# RFBoardLayoutGen0_v03_3JK2.net
KiCad netlist of a schematic drawn in EAGLE
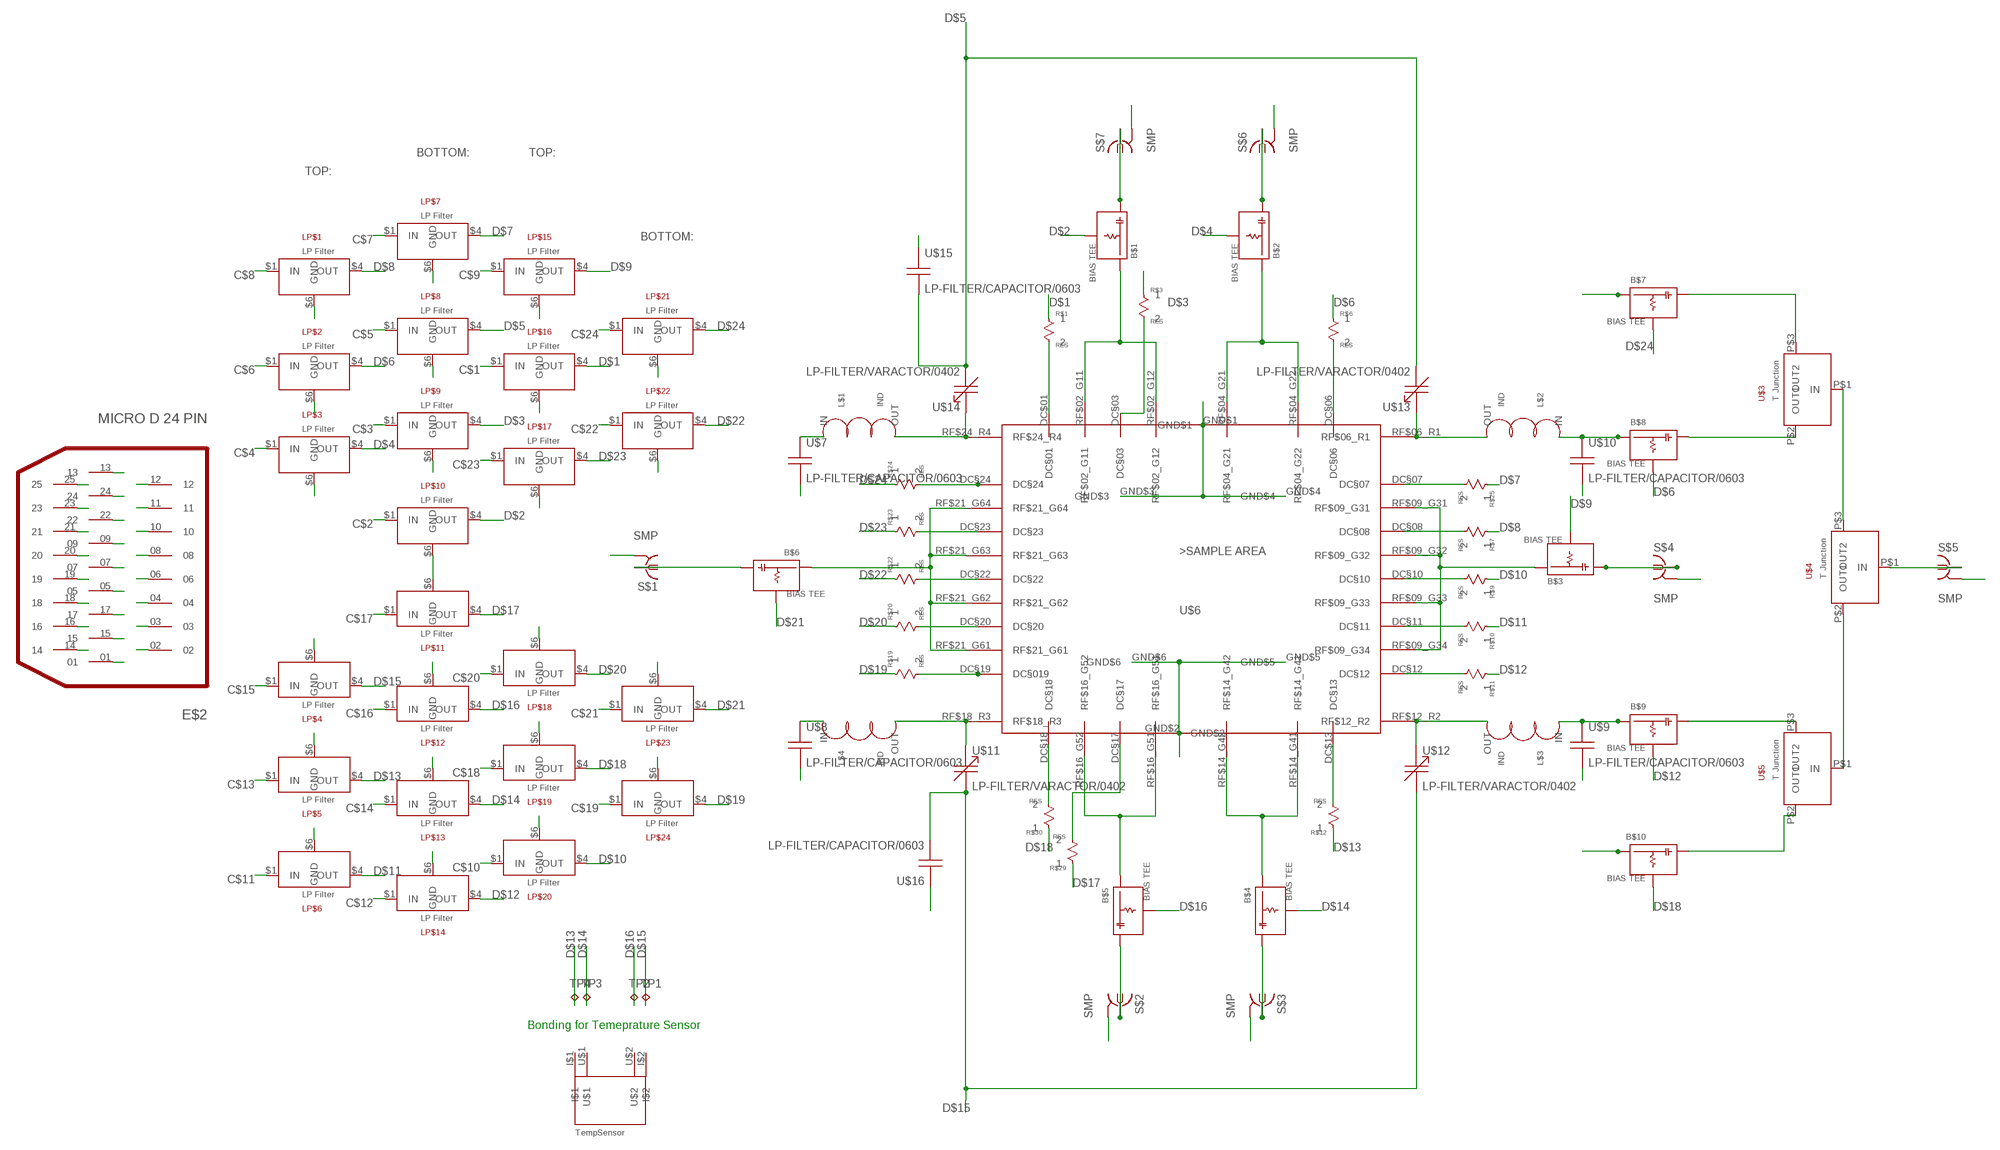
[diagram p0: schematic, sheet 1, part 1 of 2]
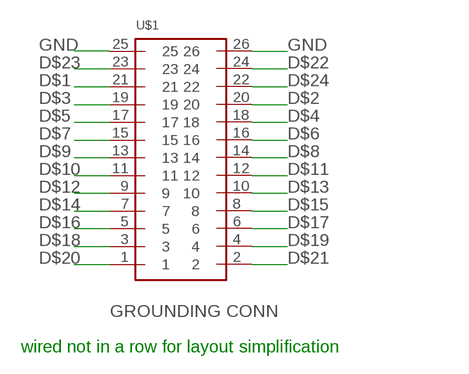
[diagram p1: schematic, sheet 1, part 2 of 2]

(export (version "E")
  (design (tool "Eeschema 10.0.6"))
  (components
    (comp (ref "B$1")
      (value "BIASTEEDOWN")
      (footprint "eagle-import:BIAS_TEE_DOWN_0603")
      (libsource (lib "eagle-import") (part "BIASTEEDOWN"))
    )
    (comp (ref "B$2")
      (value "BIASTEEUP")
      (footprint "eagle-import:BIAS_TEE_UP_0603")
      (libsource (lib "eagle-import") (part "BIASTEEUP"))
    )
    (comp (ref "B$3")
      (value "BIASTEEDOWN")
      (footprint "eagle-import:BIAS_TEE_DOWN_0603")
      (libsource (lib "eagle-import") (part "BIASTEEDOWN"))
    )
    (comp (ref "B$4")
      (value "BIASTEEDOWN")
      (footprint "eagle-import:BIAS_TEE_DOWN_0603")
      (libsource (lib "eagle-import") (part "BIASTEEDOWN"))
    )
    (comp (ref "B$5")
      (value "BIASTEEUP")
      (footprint "eagle-import:BIAS_TEE_UP_0603")
      (libsource (lib "eagle-import") (part "BIASTEEUP"))
    )
    (comp (ref "B$6")
      (value "BIASTEEDOWN")
      (footprint "eagle-import:BIAS_TEE_DOWN_0603")
      (libsource (lib "eagle-import") (part "BIASTEEDOWN"))
    )
    (comp (ref "B$7")
      (value "BIASTEEUP")
      (footprint "eagle-import:BIAS_TEE_UP_0603")
      (libsource (lib "eagle-import") (part "BIASTEEUP"))
    )
    (comp (ref "B$8")
      (value "BIASTEEDOWN")
      (footprint "eagle-import:BIAS_TEE_DOWN_0603")
      (libsource (lib "eagle-import") (part "BIASTEEDOWN"))
    )
    (comp (ref "B$9")
      (value "BIASTEEUP")
      (footprint "eagle-import:BIAS_TEE_UP_0603")
      (libsource (lib "eagle-import") (part "BIASTEEUP"))
    )
    (comp (ref "B$10")
      (value "BIASTEEDOWN")
      (footprint "eagle-import:BIAS_TEE_DOWN_0603")
      (libsource (lib "eagle-import") (part "BIASTEEDOWN"))
    )
    (comp (ref "E$2")
      (value "25_SOCKET_M83513(13-DPINOUT2")
      (footprint "eagle-import:25_SOCKET_M83513_13-D_V2")
      (libsource (lib "eagle-import") (part "25_SOCKET_M83513(13-DPINOUT2"))
    )
    (comp (ref "L$1")
      (value "L_MATCH")
      (footprint "eagle-import:L_MATCH")
      (libsource (lib "eagle-import") (part "L_MATCH"))
    )
    (comp (ref "L$2")
      (value "L_MATCH")
      (footprint "eagle-import:L_MATCH")
      (libsource (lib "eagle-import") (part "L_MATCH"))
    )
    (comp (ref "L$3")
      (value "L_MATCH")
      (footprint "eagle-import:L_MATCH")
      (libsource (lib "eagle-import") (part "L_MATCH"))
    )
    (comp (ref "L$4")
      (value "L_MATCH")
      (footprint "eagle-import:L_MATCH")
      (libsource (lib "eagle-import") (part "L_MATCH"))
    )
    (comp (ref "LP$1")
      (value "LP-FILTER/1-STAGETOP")
      (footprint "eagle-import:LP-FILTER_1_STAGE_OS_0603_TOP")
      (libsource (lib "eagle-import") (part "LP-FILTER/1-STAGETOP"))
    )
    (comp (ref "LP$2")
      (value "LP-FILTER/1-STAGETOP")
      (footprint "eagle-import:LP-FILTER_1_STAGE_OS_0603_TOP")
      (libsource (lib "eagle-import") (part "LP-FILTER/1-STAGETOP"))
    )
    (comp (ref "LP$3")
      (value "LP-FILTER/1-STAGETOP")
      (footprint "eagle-import:LP-FILTER_1_STAGE_OS_0603_TOP")
      (libsource (lib "eagle-import") (part "LP-FILTER/1-STAGETOP"))
    )
    (comp (ref "LP$4")
      (value "LP-FILTER/1-STAGETOP")
      (footprint "eagle-import:LP-FILTER_1_STAGE_OS_0603_TOP")
      (libsource (lib "eagle-import") (part "LP-FILTER/1-STAGETOP"))
    )
    (comp (ref "LP$5")
      (value "LP-FILTER/1-STAGETOP")
      (footprint "eagle-import:LP-FILTER_1_STAGE_OS_0603_TOP")
      (libsource (lib "eagle-import") (part "LP-FILTER/1-STAGETOP"))
    )
    (comp (ref "LP$6")
      (value "LP-FILTER/1-STAGETOP")
      (footprint "eagle-import:LP-FILTER_1_STAGE_OS_0603_TOP")
      (libsource (lib "eagle-import") (part "LP-FILTER/1-STAGETOP"))
    )
    (comp (ref "LP$7")
      (value "LP-FILTER/1-STAGEBOT")
      (footprint "eagle-import:LP-FILTER_1_STAGE_OS_0603_BOTTOM")
      (libsource (lib "eagle-import") (part "LP-FILTER/1-STAGEBOT"))
    )
    (comp (ref "LP$8")
      (value "LP-FILTER/1-STAGEBOT")
      (footprint "eagle-import:LP-FILTER_1_STAGE_OS_0603_BOTTOM")
      (libsource (lib "eagle-import") (part "LP-FILTER/1-STAGEBOT"))
    )
    (comp (ref "LP$9")
      (value "LP-FILTER/1-STAGEBOT")
      (footprint "eagle-import:LP-FILTER_1_STAGE_OS_0603_BOTTOM")
      (libsource (lib "eagle-import") (part "LP-FILTER/1-STAGEBOT"))
    )
    (comp (ref "LP$10")
      (value "LP-FILTER/1-STAGEBOT")
      (footprint "eagle-import:LP-FILTER_1_STAGE_OS_0603_BOTTOM")
      (libsource (lib "eagle-import") (part "LP-FILTER/1-STAGEBOT"))
    )
    (comp (ref "LP$11")
      (value "LP-FILTER/1-STAGEBOT")
      (footprint "eagle-import:LP-FILTER_1_STAGE_OS_0603_BOTTOM")
      (libsource (lib "eagle-import") (part "LP-FILTER/1-STAGEBOT"))
    )
    (comp (ref "LP$12")
      (value "LP-FILTER/1-STAGEBOT")
      (footprint "eagle-import:LP-FILTER_1_STAGE_OS_0603_BOTTOM")
      (libsource (lib "eagle-import") (part "LP-FILTER/1-STAGEBOT"))
    )
    (comp (ref "LP$13")
      (value "LP-FILTER/1-STAGEBOT")
      (footprint "eagle-import:LP-FILTER_1_STAGE_OS_0603_BOTTOM")
      (libsource (lib "eagle-import") (part "LP-FILTER/1-STAGEBOT"))
    )
    (comp (ref "LP$14")
      (value "LP-FILTER/1-STAGEBOT")
      (footprint "eagle-import:LP-FILTER_1_STAGE_OS_0603_BOTTOM")
      (libsource (lib "eagle-import") (part "LP-FILTER/1-STAGEBOT"))
    )
    (comp (ref "LP$15")
      (value "LP-FILTER/1-STAGETOP")
      (footprint "eagle-import:LP-FILTER_1_STAGE_OS_0603_TOP")
      (libsource (lib "eagle-import") (part "LP-FILTER/1-STAGETOP"))
    )
    (comp (ref "LP$16")
      (value "LP-FILTER/1-STAGETOP")
      (footprint "eagle-import:LP-FILTER_1_STAGE_OS_0603_TOP")
      (libsource (lib "eagle-import") (part "LP-FILTER/1-STAGETOP"))
    )
    (comp (ref "LP$17")
      (value "LP-FILTER/1-STAGETOP")
      (footprint "eagle-import:LP-FILTER_1_STAGE_OS_0603_TOP")
      (libsource (lib "eagle-import") (part "LP-FILTER/1-STAGETOP"))
    )
    (comp (ref "LP$18")
      (value "LP-FILTER/1-STAGETOP")
      (footprint "eagle-import:LP-FILTER_1_STAGE_OS_0603_TOP")
      (libsource (lib "eagle-import") (part "LP-FILTER/1-STAGETOP"))
    )
    (comp (ref "LP$19")
      (value "LP-FILTER/1-STAGETOP")
      (footprint "eagle-import:LP-FILTER_1_STAGE_OS_0603_TOP")
      (libsource (lib "eagle-import") (part "LP-FILTER/1-STAGETOP"))
    )
    (comp (ref "LP$20")
      (value "LP-FILTER/1-STAGETOP")
      (footprint "eagle-import:LP-FILTER_1_STAGE_OS_0603_TOP")
      (libsource (lib "eagle-import") (part "LP-FILTER/1-STAGETOP"))
    )
    (comp (ref "LP$21")
      (value "LP-FILTER/1-STAGEBOT")
      (footprint "eagle-import:LP-FILTER_1_STAGE_OS_0603_BOTTOM")
      (libsource (lib "eagle-import") (part "LP-FILTER/1-STAGEBOT"))
    )
    (comp (ref "LP$22")
      (value "LP-FILTER/1-STAGEBOT")
      (footprint "eagle-import:LP-FILTER_1_STAGE_OS_0603_BOTTOM")
      (libsource (lib "eagle-import") (part "LP-FILTER/1-STAGEBOT"))
    )
    (comp (ref "LP$23")
      (value "LP-FILTER/1-STAGEBOT")
      (footprint "eagle-import:LP-FILTER_1_STAGE_OS_0603_BOTTOM")
      (libsource (lib "eagle-import") (part "LP-FILTER/1-STAGEBOT"))
    )
    (comp (ref "LP$24")
      (value "LP-FILTER/1-STAGEBOT")
      (footprint "eagle-import:LP-FILTER_1_STAGE_OS_0603_BOTTOM")
      (libsource (lib "eagle-import") (part "LP-FILTER/1-STAGEBOT"))
    )
    (comp (ref "R$1")
      (value "10K")
      (footprint "eagle-import:LP-FILTER_RESISTOR_0603_BOTTOM")
      (libsource (lib "eagle-import") (part "LP-FILTER/RESISTOR/0603"))
    )
    (comp (ref "R$3")
      (value "10K")
      (footprint "eagle-import:LP-FILTER_RESISTOR_0603_BOTTOM")
      (libsource (lib "eagle-import") (part "LP-FILTER/RESISTOR/0603"))
    )
    (comp (ref "R$6")
      (value "10K")
      (footprint "eagle-import:LP-FILTER_RESISTOR_0603_BOTTOM")
      (libsource (lib "eagle-import") (part "LP-FILTER/RESISTOR/0603"))
    )
    (comp (ref "R$7")
      (value "10K")
      (footprint "eagle-import:LP-FILTER_RESISTOR_0603_BOTTOM")
      (libsource (lib "eagle-import") (part "LP-FILTER/RESISTOR/0603"))
    )
    (comp (ref "R$9")
      (value "10K")
      (footprint "eagle-import:LP-FILTER_RESISTOR_0603_BOTTOM")
      (libsource (lib "eagle-import") (part "LP-FILTER/RESISTOR/0603"))
    )
    (comp (ref "R$10")
      (value "10K")
      (footprint "eagle-import:LP-FILTER_RESISTOR_0603_BOTTOM")
      (libsource (lib "eagle-import") (part "LP-FILTER/RESISTOR/0603"))
    )
    (comp (ref "R$11")
      (value "10K")
      (footprint "eagle-import:LP-FILTER_RESISTOR_0603_BOTTOM")
      (libsource (lib "eagle-import") (part "LP-FILTER/RESISTOR/0603"))
    )
    (comp (ref "R$12")
      (value "10K")
      (footprint "eagle-import:LP-FILTER_RESISTOR_0603_BOTTOM")
      (libsource (lib "eagle-import") (part "LP-FILTER/RESISTOR/0603"))
    )
    (comp (ref "R$19")
      (value "10K")
      (footprint "eagle-import:LP-FILTER_RESISTOR_0603_BOTTOM")
      (libsource (lib "eagle-import") (part "LP-FILTER/RESISTOR/0603"))
    )
    (comp (ref "R$20")
      (value "10K")
      (footprint "eagle-import:LP-FILTER_RESISTOR_0603_BOTTOM")
      (libsource (lib "eagle-import") (part "LP-FILTER/RESISTOR/0603"))
    )
    (comp (ref "R$22")
      (value "10K")
      (footprint "eagle-import:LP-FILTER_RESISTOR_0603_BOTTOM")
      (libsource (lib "eagle-import") (part "LP-FILTER/RESISTOR/0603"))
    )
    (comp (ref "R$23")
      (value "10K")
      (footprint "eagle-import:LP-FILTER_RESISTOR_0603_BOTTOM")
      (libsource (lib "eagle-import") (part "LP-FILTER/RESISTOR/0603"))
    )
    (comp (ref "R$24")
      (value "10K")
      (footprint "eagle-import:LP-FILTER_RESISTOR_0603_BOTTOM")
      (libsource (lib "eagle-import") (part "LP-FILTER/RESISTOR/0603"))
    )
    (comp (ref "R$25")
      (value "10K")
      (footprint "eagle-import:LP-FILTER_RESISTOR_0603_BOTTOM")
      (libsource (lib "eagle-import") (part "LP-FILTER/RESISTOR/0603"))
    )
    (comp (ref "R$29")
      (value "10K")
      (footprint "eagle-import:LP-FILTER_RESISTOR_0603_BOTTOM")
      (libsource (lib "eagle-import") (part "LP-FILTER/RESISTOR/0603"))
    )
    (comp (ref "R$30")
      (value "10K")
      (footprint "eagle-import:LP-FILTER_RESISTOR_0603_BOTTOM")
      (libsource (lib "eagle-import") (part "LP-FILTER/RESISTOR/0603"))
    )
    (comp (ref "S$1")
      (value "MC-921WIDE")
      (footprint "eagle-import:SMP_STRAIGHT_MINI_WIDE")
      (libsource (lib "eagle-import") (part "MC-921WIDE"))
    )
    (comp (ref "S$2")
      (value "MC-921WIDE")
      (footprint "eagle-import:SMP_STRAIGHT_MINI_WIDE")
      (libsource (lib "eagle-import") (part "MC-921WIDE"))
    )
    (comp (ref "S$3")
      (value "MC-921WIDE")
      (footprint "eagle-import:SMP_STRAIGHT_MINI_WIDE")
      (libsource (lib "eagle-import") (part "MC-921WIDE"))
    )
    (comp (ref "S$4")
      (value "MC-921WIDE")
      (footprint "eagle-import:SMP_STRAIGHT_MINI_WIDE")
      (libsource (lib "eagle-import") (part "MC-921WIDE"))
    )
    (comp (ref "S$5")
      (value "MC-921WIDE")
      (footprint "eagle-import:SMP_STRAIGHT_MINI_WIDE")
      (libsource (lib "eagle-import") (part "MC-921WIDE"))
    )
    (comp (ref "S$6")
      (value "MC-921WIDE")
      (footprint "eagle-import:SMP_STRAIGHT_MINI_WIDE")
      (libsource (lib "eagle-import") (part "MC-921WIDE"))
    )
    (comp (ref "S$7")
      (value "MC-921WIDE")
      (footprint "eagle-import:SMP_STRAIGHT_MINI_WIDE")
      (libsource (lib "eagle-import") (part "MC-921WIDE"))
    )
    (comp (ref "TP1")
      (value "TPTP07SQ")
      (footprint "eagle-import:TP07SQ")
      (libsource (lib "eagle-import") (part "TPTP07SQ"))
    )
    (comp (ref "TP2")
      (value "TPTP07SQ")
      (footprint "eagle-import:TP07SQ")
      (libsource (lib "eagle-import") (part "TPTP07SQ"))
    )
    (comp (ref "TP3")
      (value "TPTP07SQ")
      (footprint "eagle-import:TP07SQ")
      (libsource (lib "eagle-import") (part "TPTP07SQ"))
    )
    (comp (ref "TP4")
      (value "TPTP07SQ")
      (footprint "eagle-import:TP07SQ")
      (libsource (lib "eagle-import") (part "TPTP07SQ"))
    )
    (comp (ref "U$1")
      (value "MEC8-113-02-L-D-RA1MBRD")
      (footprint "eagle-import:MEC8-113-02-L-D-RA1")
      (libsource (lib "eagle-import") (part "MEC8-113-02-L-D-RA1MBRD"))
    )
    (comp (ref "U$2")
      (value "TEMPSENS")
      (footprint "eagle-import:RX-BR_V1")
      (libsource (lib "eagle-import") (part "TEMPSENS"))
    )
    (comp (ref "U$3")
      (value "TJUNCTION")
      (footprint "eagle-import:T_JUNCTION_0.3MM")
      (libsource (lib "eagle-import") (part "TJUNCTION"))
    )
    (comp (ref "U$4")
      (value "TJUNCTION")
      (footprint "eagle-import:T_JUNCTION_0.3MM")
      (libsource (lib "eagle-import") (part "TJUNCTION"))
    )
    (comp (ref "U$5")
      (value "TJUNCTION")
      (footprint "eagle-import:T_JUNCTION_0.3MM")
      (libsource (lib "eagle-import") (part "TJUNCTION"))
    )
    (comp (ref "U$6")
      (value "24DC+10RF_V2.0")
      (footprint "eagle-import:24DC+10RF_400MU-PADS_0.7X0.7_V2.0")
      (libsource (lib "eagle-import") (part "24DC+10RF_V2.0"))
    )
    (comp (ref "U$7")
      (value "LP-FILTER/CAPACITOR/0603")
      (footprint "eagle-import:LP-FILTER_CAPACITOR_0603_BOTTOM")
      (libsource (lib "eagle-import") (part "LP-FILTER/CAPACITOR/0603"))
    )
    (comp (ref "U$8")
      (value "LP-FILTER/CAPACITOR/0603")
      (footprint "eagle-import:LP-FILTER_CAPACITOR_0603_BOTTOM")
      (libsource (lib "eagle-import") (part "LP-FILTER/CAPACITOR/0603"))
    )
    (comp (ref "U$9")
      (value "LP-FILTER/CAPACITOR/0603")
      (footprint "eagle-import:LP-FILTER_CAPACITOR_0603_BOTTOM")
      (libsource (lib "eagle-import") (part "LP-FILTER/CAPACITOR/0603"))
    )
    (comp (ref "U$10")
      (value "LP-FILTER/CAPACITOR/0603")
      (footprint "eagle-import:LP-FILTER_CAPACITOR_0603_BOTTOM")
      (libsource (lib "eagle-import") (part "LP-FILTER/CAPACITOR/0603"))
    )
    (comp (ref "U$11")
      (value "LP-FILTER/VARACTOR/0402")
      (footprint "eagle-import:LP-FILTER_VARACTOR_0402")
      (libsource (lib "eagle-import") (part "LP-FILTER/VARACTOR/0402"))
    )
    (comp (ref "U$12")
      (value "LP-FILTER/VARACTOR/0402")
      (footprint "eagle-import:LP-FILTER_VARACTOR_0402")
      (libsource (lib "eagle-import") (part "LP-FILTER/VARACTOR/0402"))
    )
    (comp (ref "U$13")
      (value "LP-FILTER/VARACTOR/0402")
      (footprint "eagle-import:LP-FILTER_VARACTOR_0402")
      (libsource (lib "eagle-import") (part "LP-FILTER/VARACTOR/0402"))
    )
    (comp (ref "U$14")
      (value "LP-FILTER/VARACTOR/0402")
      (footprint "eagle-import:LP-FILTER_VARACTOR_0402")
      (libsource (lib "eagle-import") (part "LP-FILTER/VARACTOR/0402"))
    )
    (comp (ref "U$15")
      (value "LP-FILTER/CAPACITOR/0603")
      (footprint "eagle-import:LP-FILTER_CAPACITOR_0603_BOTTOM")
      (libsource (lib "eagle-import") (part "LP-FILTER/CAPACITOR/0603"))
    )
    (comp (ref "U$16")
      (value "LP-FILTER/CAPACITOR/0603")
      (footprint "eagle-import:LP-FILTER_CAPACITOR_0603_BOTTOM")
      (libsource (lib "eagle-import") (part "LP-FILTER/CAPACITOR/0603"))
    )
  )
  (nets
    (net (code "1") (name "/C$1") (class "Default")
      (node (ref "E$2") (pin "01") (pinfunction "01_01") (pintype "bidirectional"))
      (node (ref "LP$16") (pin "$1") (pinfunction "IN_$1") (pintype "bidirectional"))
    )
    (net (code "2") (name "/C$2") (class "Default")
      (node (ref "E$2") (pin "02") (pinfunction "02_02") (pintype "bidirectional"))
      (node (ref "LP$10") (pin "$1") (pinfunction "IN_$1") (pintype "bidirectional"))
    )
    (net (code "3") (name "/C$3") (class "Default")
      (node (ref "E$2") (pin "03") (pinfunction "03_03") (pintype "bidirectional"))
      (node (ref "LP$9") (pin "$1") (pinfunction "IN_$1") (pintype "bidirectional"))
    )
    (net (code "4") (name "/C$4") (class "Default")
      (node (ref "E$2") (pin "04") (pinfunction "04_04") (pintype "bidirectional"))
      (node (ref "LP$3") (pin "$1") (pinfunction "IN_$1") (pintype "bidirectional"))
    )
    (net (code "5") (name "/C$5") (class "Default")
      (node (ref "E$2") (pin "05") (pinfunction "05_05") (pintype "bidirectional"))
      (node (ref "LP$8") (pin "$1") (pinfunction "IN_$1") (pintype "bidirectional"))
    )
    (net (code "6") (name "/C$6") (class "Default")
      (node (ref "E$2") (pin "06") (pinfunction "06_06") (pintype "bidirectional"))
      (node (ref "LP$2") (pin "$1") (pinfunction "IN_$1") (pintype "bidirectional"))
    )
    (net (code "7") (name "/C$7") (class "Default")
      (node (ref "E$2") (pin "07") (pinfunction "07_07") (pintype "bidirectional"))
      (node (ref "LP$7") (pin "$1") (pinfunction "IN_$1") (pintype "bidirectional"))
    )
    (net (code "8") (name "/C$8") (class "Default")
      (node (ref "E$2") (pin "08") (pinfunction "08_08") (pintype "bidirectional"))
      (node (ref "LP$1") (pin "$1") (pinfunction "IN_$1") (pintype "bidirectional"))
    )
    (net (code "9") (name "/C$9") (class "Default")
      (node (ref "E$2") (pin "09") (pinfunction "09_09") (pintype "bidirectional"))
      (node (ref "LP$15") (pin "$1") (pinfunction "IN_$1") (pintype "bidirectional"))
    )
    (net (code "10") (name "/C$10") (class "Default")
      (node (ref "E$2") (pin "10") (pinfunction "10_10") (pintype "bidirectional"))
      (node (ref "LP$20") (pin "$1") (pinfunction "IN_$1") (pintype "bidirectional"))
    )
    (net (code "11") (name "/C$11") (class "Default")
      (node (ref "E$2") (pin "11") (pinfunction "11_11") (pintype "bidirectional"))
      (node (ref "LP$6") (pin "$1") (pinfunction "IN_$1") (pintype "bidirectional"))
    )
    (net (code "12") (name "/C$12") (class "Default")
      (node (ref "E$2") (pin "12") (pinfunction "12_12") (pintype "bidirectional"))
      (node (ref "LP$14") (pin "$1") (pinfunction "IN_$1") (pintype "bidirectional"))
    )
    (net (code "13") (name "/C$13") (class "Default")
      (node (ref "E$2") (pin "13") (pinfunction "13_13") (pintype "bidirectional"))
      (node (ref "LP$5") (pin "$1") (pinfunction "IN_$1") (pintype "bidirectional"))
    )
    (net (code "14") (name "/C$14") (class "Default")
      (node (ref "E$2") (pin "14") (pinfunction "14_14") (pintype "bidirectional"))
      (node (ref "LP$13") (pin "$1") (pinfunction "IN_$1") (pintype "bidirectional"))
    )
    (net (code "15") (name "/C$15") (class "Default")
      (node (ref "E$2") (pin "15") (pinfunction "15_15") (pintype "bidirectional"))
      (node (ref "LP$4") (pin "$1") (pinfunction "IN_$1") (pintype "bidirectional"))
    )
    (net (code "16") (name "/C$16") (class "Default")
      (node (ref "E$2") (pin "16") (pinfunction "16_16") (pintype "bidirectional"))
      (node (ref "LP$12") (pin "$1") (pinfunction "IN_$1") (pintype "bidirectional"))
    )
    (net (code "17") (name "/C$17") (class "Default")
      (node (ref "E$2") (pin "17") (pinfunction "17_17") (pintype "bidirectional"))
      (node (ref "LP$11") (pin "$1") (pinfunction "IN_$1") (pintype "bidirectional"))
    )
    (net (code "18") (name "/C$18") (class "Default")
      (node (ref "E$2") (pin "18") (pinfunction "18_18") (pintype "bidirectional"))
      (node (ref "LP$19") (pin "$1") (pinfunction "IN_$1") (pintype "bidirectional"))
    )
    (net (code "19") (name "/C$19") (class "Default")
      (node (ref "E$2") (pin "19") (pinfunction "19_19") (pintype "bidirectional"))
      (node (ref "LP$24") (pin "$1") (pinfunction "IN_$1") (pintype "bidirectional"))
    )
    (net (code "20") (name "/C$20") (class "Default")
      (node (ref "E$2") (pin "20") (pinfunction "20_20") (pintype "bidirectional"))
      (node (ref "LP$18") (pin "$1") (pinfunction "IN_$1") (pintype "bidirectional"))
    )
    (net (code "21") (name "/C$21") (class "Default")
      (node (ref "E$2") (pin "21") (pinfunction "21_21") (pintype "bidirectional"))
      (node (ref "LP$23") (pin "$1") (pinfunction "IN_$1") (pintype "bidirectional"))
    )
    (net (code "22") (name "/C$22") (class "Default")
      (node (ref "E$2") (pin "22") (pinfunction "22_22") (pintype "bidirectional"))
      (node (ref "LP$22") (pin "$1") (pinfunction "IN_$1") (pintype "bidirectional"))
    )
    (net (code "23") (name "/C$23") (class "Default")
      (node (ref "E$2") (pin "23") (pinfunction "23_23") (pintype "bidirectional"))
      (node (ref "LP$17") (pin "$1") (pinfunction "IN_$1") (pintype "bidirectional"))
    )
    (net (code "24") (name "/C$24") (class "Default")
      (node (ref "E$2") (pin "24") (pinfunction "24_24") (pintype "bidirectional"))
      (node (ref "LP$21") (pin "$1") (pinfunction "IN_$1") (pintype "bidirectional"))
    )
    (net (code "25") (name "/D$1") (class "Default")
      (node (ref "LP$16") (pin "$4") (pinfunction "OUT_$4") (pintype "bidirectional"))
      (node (ref "R$1") (pin "IN") (pinfunction "1_IN") (pintype "passive"))
      (node (ref "U$1") (pin "21") (pinfunction "21_21") (pintype "bidirectional"))
    )
    (net (code "26") (name "/D$2") (class "Default")
      (node (ref "B$1") (pin "LF") (pinfunction "LF_LF") (pintype "bidirectional"))
      (node (ref "LP$10") (pin "$4") (pinfunction "OUT_$4") (pintype "bidirectional"))
      (node (ref "U$1") (pin "20") (pinfunction "20_20") (pintype "bidirectional"))
    )
    (net (code "27") (name "/D$3") (class "Default")
      (node (ref "LP$9") (pin "$4") (pinfunction "OUT_$4") (pintype "bidirectional"))
      (node (ref "R$3") (pin "IN") (pinfunction "1_IN") (pintype "passive"))
      (node (ref "U$1") (pin "19") (pinfunction "19_19") (pintype "bidirectional"))
    )
    (net (code "28") (name "/D$4") (class "Default")
      (node (ref "B$2") (pin "LF") (pinfunction "LF_LF") (pintype "bidirectional"))
      (node (ref "LP$3") (pin "$4") (pinfunction "OUT_$4") (pintype "bidirectional"))
      (node (ref "U$1") (pin "18") (pinfunction "18_18") (pintype "bidirectional"))
    )
    (net (code "29") (name "/D$5") (class "Default")
      (node (ref "LP$8") (pin "$4") (pinfunction "OUT_$4") (pintype "bidirectional"))
      (node (ref "U$1") (pin "17") (pinfunction "17_17") (pintype "bidirectional"))
      (node (ref "U$13") (pin "OUT") (pinfunction "2_OUT") (pintype "passive"))
      (node (ref "U$14") (pin "OUT") (pinfunction "2_OUT") (pintype "passive"))
      (node (ref "U$15") (pin "OUT") (pinfunction "2_OUT") (pintype "passive"))
    )
    (net (code "30") (name "/D$6") (class "Default")
      (node (ref "B$8") (pin "LF") (pinfunction "LF_LF") (pintype "bidirectional"))
      (node (ref "LP$2") (pin "$4") (pinfunction "OUT_$4") (pintype "bidirectional"))
      (node (ref "R$6") (pin "IN") (pinfunction "1_IN") (pintype "passive"))
      (node (ref "U$1") (pin "16") (pinfunction "16_16") (pintype "bidirectional"))
    )
    (net (code "31") (name "/D$7") (class "Default")
      (node (ref "LP$7") (pin "$4") (pinfunction "OUT_$4") (pintype "bidirectional"))
      (node (ref "R$25") (pin "IN") (pinfunction "1_IN") (pintype "passive"))
      (node (ref "U$1") (pin "15") (pinfunction "15_15") (pintype "bidirectional"))
    )
    (net (code "32") (name "/D$8") (class "Default")
      (node (ref "LP$1") (pin "$4") (pinfunction "OUT_$4") (pintype "bidirectional"))
      (node (ref "R$7") (pin "IN") (pinfunction "1_IN") (pintype "passive"))
      (node (ref "U$1") (pin "14") (pinfunction "14_14") (pintype "bidirectional"))
    )
    (net (code "33") (name "/D$9") (class "Default")
      (node (ref "B$3") (pin "LF") (pinfunction "LF_LF") (pintype "bidirectional"))
      (node (ref "LP$15") (pin "$4") (pinfunction "OUT_$4") (pintype "bidirectional"))
      (node (ref "U$1") (pin "13") (pinfunction "13_13") (pintype "bidirectional"))
    )
    (net (code "34") (name "/D$10") (class "Default")
      (node (ref "LP$20") (pin "$4") (pinfunction "OUT_$4") (pintype "bidirectional"))
      (node (ref "R$9") (pin "IN") (pinfunction "1_IN") (pintype "passive"))
      (node (ref "U$1") (pin "11") (pinfunction "11_11") (pintype "bidirectional"))
    )
    (net (code "35") (name "/D$11") (class "Default")
      (node (ref "LP$6") (pin "$4") (pinfunction "OUT_$4") (pintype "bidirectional"))
      (node (ref "R$10") (pin "IN") (pinfunction "1_IN") (pintype "passive"))
      (node (ref "U$1") (pin "12") (pinfunction "12_12") (pintype "bidirectional"))
    )
    (net (code "36") (name "/D$12") (class "Default")
      (node (ref "B$9") (pin "LF") (pinfunction "LF_LF") (pintype "bidirectional"))
      (node (ref "LP$14") (pin "$4") (pinfunction "OUT_$4") (pintype "bidirectional"))
      (node (ref "R$11") (pin "IN") (pinfunction "1_IN") (pintype "passive"))
      (node (ref "U$1") (pin "9") (pinfunction "9_9") (pintype "bidirectional"))
    )
    (net (code "37") (name "/D$13") (class "Default")
      (node (ref "LP$5") (pin "$4") (pinfunction "OUT_$4") (pintype "bidirectional"))
      (node (ref "R$12") (pin "IN") (pinfunction "1_IN") (pintype "passive"))
      (node (ref "TP4") (pin "TP") (pinfunction "TP_TP") (pintype "input"))
      (node (ref "U$1") (pin "10") (pinfunction "10_10") (pintype "bidirectional"))
    )
    (net (code "38") (name "/D$14") (class "Default")
      (node (ref "B$4") (pin "LF") (pinfunction "LF_LF") (pintype "bidirectional"))
      (node (ref "LP$13") (pin "$4") (pinfunction "OUT_$4") (pintype "bidirectional"))
      (node (ref "TP3") (pin "TP") (pinfunction "TP_TP") (pintype "input"))
      (node (ref "U$1") (pin "7") (pinfunction "7_7") (pintype "bidirectional"))
    )
    (net (code "39") (name "/D$15") (class "Default")
      (node (ref "LP$4") (pin "$4") (pinfunction "OUT_$4") (pintype "bidirectional"))
      (node (ref "TP1") (pin "TP") (pinfunction "TP_TP") (pintype "input"))
      (node (ref "U$1") (pin "8") (pinfunction "8_8") (pintype "bidirectional"))
      (node (ref "U$11") (pin "OUT") (pinfunction "2_OUT") (pintype "passive"))
      (node (ref "U$12") (pin "OUT") (pinfunction "2_OUT") (pintype "passive"))
      (node (ref "U$16") (pin "OUT") (pinfunction "2_OUT") (pintype "passive"))
    )
    (net (code "40") (name "/D$16") (class "Default")
      (node (ref "B$5") (pin "LF") (pinfunction "LF_LF") (pintype "bidirectional"))
      (node (ref "LP$12") (pin "$4") (pinfunction "OUT_$4") (pintype "bidirectional"))
      (node (ref "TP2") (pin "TP") (pinfunction "TP_TP") (pintype "input"))
      (node (ref "U$1") (pin "5") (pinfunction "5_5") (pintype "bidirectional"))
    )
    (net (code "41") (name "/D$17") (class "Default")
      (node (ref "LP$11") (pin "$4") (pinfunction "OUT_$4") (pintype "bidirectional"))
      (node (ref "R$29") (pin "IN") (pinfunction "1_IN") (pintype "passive"))
      (node (ref "U$1") (pin "6") (pinfunction "6_6") (pintype "bidirectional"))
    )
    (net (code "42") (name "/D$18") (class "Default")
      (node (ref "B$10") (pin "LF") (pinfunction "LF_LF") (pintype "bidirectional"))
      (node (ref "LP$19") (pin "$4") (pinfunction "OUT_$4") (pintype "bidirectional"))
      (node (ref "R$30") (pin "IN") (pinfunction "1_IN") (pintype "passive"))
      (node (ref "U$1") (pin "3") (pinfunction "3_3") (pintype "bidirectional"))
    )
    (net (code "43") (name "/D$19") (class "Default")
      (node (ref "LP$24") (pin "$4") (pinfunction "OUT_$4") (pintype "bidirectional"))
      (node (ref "R$19") (pin "IN") (pinfunction "1_IN") (pintype "passive"))
      (node (ref "U$1") (pin "4") (pinfunction "4_4") (pintype "bidirectional"))
    )
    (net (code "44") (name "/D$20") (class "Default")
      (node (ref "LP$18") (pin "$4") (pinfunction "OUT_$4") (pintype "bidirectional"))
      (node (ref "R$20") (pin "IN") (pinfunction "1_IN") (pintype "passive"))
      (node (ref "U$1") (pin "1") (pinfunction "1_1") (pintype "bidirectional"))
    )
    (net (code "45") (name "/D$21") (class "Default")
      (node (ref "B$6") (pin "LF") (pinfunction "LF_LF") (pintype "bidirectional"))
      (node (ref "LP$23") (pin "$4") (pinfunction "OUT_$4") (pintype "bidirectional"))
      (node (ref "U$1") (pin "2") (pinfunction "2_2") (pintype "bidirectional"))
    )
    (net (code "46") (name "/D$22") (class "Default")
      (node (ref "LP$22") (pin "$4") (pinfunction "OUT_$4") (pintype "bidirectional"))
      (node (ref "R$22") (pin "IN") (pinfunction "1_IN") (pintype "passive"))
      (node (ref "U$1") (pin "24") (pinfunction "24_24") (pintype "bidirectional"))
    )
    (net (code "47") (name "/D$23") (class "Default")
      (node (ref "LP$17") (pin "$4") (pinfunction "OUT_$4") (pintype "bidirectional"))
      (node (ref "R$23") (pin "IN") (pinfunction "1_IN") (pintype "passive"))
      (node (ref "U$1") (pin "23") (pinfunction "23_23") (pintype "bidirectional"))
    )
    (net (code "48") (name "/D$24") (class "Default")
      (node (ref "B$7") (pin "LF") (pinfunction "LF_LF") (pintype "bidirectional"))
      (node (ref "LP$21") (pin "$4") (pinfunction "OUT_$4") (pintype "bidirectional"))
      (node (ref "R$24") (pin "IN") (pinfunction "1_IN") (pintype "passive"))
      (node (ref "U$1") (pin "22") (pinfunction "22_22") (pintype "bidirectional"))
    )
    (net (code "49") (name "/GND") (class "Default")
      (node (ref "E$2") (pin "25") (pinfunction "25_25") (pintype "bidirectional"))
      (node (ref "LP$1") (pin "$6") (pinfunction "GND_$6") (pintype "bidirectional"))
      (node (ref "LP$10") (pin "$6") (pinfunction "GND_$6") (pintype "bidirectional"))
      (node (ref "LP$11") (pin "$6") (pinfunction "GND_$6") (pintype "bidirectional"))
      (node (ref "LP$12") (pin "$6") (pinfunction "GND_$6") (pintype "bidirectional"))
      (node (ref "LP$13") (pin "$6") (pinfunction "GND_$6") (pintype "bidirectional"))
      (node (ref "LP$14") (pin "$6") (pinfunction "GND_$6") (pintype "bidirectional"))
      (node (ref "LP$15") (pin "$6") (pinfunction "GND_$6") (pintype "bidirectional"))
      (node (ref "LP$16") (pin "$6") (pinfunction "GND_$6") (pintype "bidirectional"))
      (node (ref "LP$17") (pin "$6") (pinfunction "GND_$6") (pintype "bidirectional"))
      (node (ref "LP$18") (pin "$6") (pinfunction "GND_$6") (pintype "bidirectional"))
      (node (ref "LP$19") (pin "$6") (pinfunction "GND_$6") (pintype "bidirectional"))
      (node (ref "LP$2") (pin "$6") (pinfunction "GND_$6") (pintype "bidirectional"))
      (node (ref "LP$20") (pin "$6") (pinfunction "GND_$6") (pintype "bidirectional"))
      (node (ref "LP$21") (pin "$6") (pinfunction "GND_$6") (pintype "bidirectional"))
      (node (ref "LP$22") (pin "$6") (pinfunction "GND_$6") (pintype "bidirectional"))
      (node (ref "LP$23") (pin "$6") (pinfunction "GND_$6") (pintype "bidirectional"))
      (node (ref "LP$24") (pin "$6") (pinfunction "GND_$6") (pintype "bidirectional"))
      (node (ref "LP$3") (pin "$6") (pinfunction "GND_$6") (pintype "bidirectional"))
      (node (ref "LP$4") (pin "$6") (pinfunction "GND_$6") (pintype "bidirectional"))
      (node (ref "LP$5") (pin "$6") (pinfunction "GND_$6") (pintype "bidirectional"))
      (node (ref "LP$6") (pin "$6") (pinfunction "GND_$6") (pintype "bidirectional"))
      (node (ref "LP$7") (pin "$6") (pinfunction "GND_$6") (pintype "bidirectional"))
      (node (ref "LP$8") (pin "$6") (pinfunction "GND_$6") (pintype "bidirectional"))
      (node (ref "LP$9") (pin "$6") (pinfunction "GND_$6") (pintype "bidirectional"))
      (node (ref "S$1") (pin "2@1") (pinfunction "GND_2@1") (pintype "passive"))
      (node (ref "S$1") (pin "2@2") (pinfunction "GND_2@2") (pintype "passive"))
      (node (ref "S$2") (pin "2@1") (pinfunction "GND_2@1") (pintype "passive"))
      (node (ref "S$2") (pin "2@2") (pinfunction "GND_2@2") (pintype "passive"))
      (node (ref "S$3") (pin "2@1") (pinfunction "GND_2@1") (pintype "passive"))
      (node (ref "S$3") (pin "2@2") (pinfunction "GND_2@2") (pintype "passive"))
      (node (ref "S$4") (pin "2@1") (pinfunction "GND_2@1") (pintype "passive"))
      (node (ref "S$4") (pin "2@2") (pinfunction "GND_2@2") (pintype "passive"))
      (node (ref "S$5") (pin "2@1") (pinfunction "GND_2@1") (pintype "passive"))
      (node (ref "S$5") (pin "2@2") (pinfunction "GND_2@2") (pintype "passive"))
      (node (ref "S$6") (pin "2@1") (pinfunction "GND_2@1") (pintype "passive"))
      (node (ref "S$6") (pin "2@2") (pinfunction "GND_2@2") (pintype "passive"))
      (node (ref "S$7") (pin "2@1") (pinfunction "GND_2@1") (pintype "passive"))
      (node (ref "S$7") (pin "2@2") (pinfunction "GND_2@2") (pintype "passive"))
      (node (ref "U$1") (pin "25") (pinfunction "25_25") (pintype "bidirectional"))
      (node (ref "U$1") (pin "26") (pinfunction "26_26") (pintype "bidirectional"))
      (node (ref "U$10") (pin "OUT") (pinfunction "2_OUT") (pintype "passive"))
      (node (ref "U$15") (pin "IN") (pinfunction "1_IN") (pintype "passive"))
      (node (ref "U$16") (pin "IN") (pinfunction "1_IN") (pintype "passive"))
      (node (ref "U$6") (pin "GND$1") (pinfunction "GND$1_GND$1") (pintype "bidirectional"))
      (node (ref "U$6") (pin "GND$2") (pinfunction "GND$2_GND$2") (pintype "bidirectional"))
      (node (ref "U$6") (pin "GND$3") (pinfunction "GND$3_GND$3") (pintype "bidirectional"))
      (node (ref "U$6") (pin "GND$4") (pinfunction "GND$4_GND$4") (pintype "bidirectional"))
      (node (ref "U$6") (pin "GND$5") (pinfunction "GND$5_GND$5") (pintype "bidirectional"))
      (node (ref "U$6") (pin "GND$6") (pinfunction "GND$6_GND$6") (pintype "bidirectional"))
      (node (ref "U$7") (pin "OUT") (pinfunction "2_OUT") (pintype "passive"))
      (node (ref "U$8") (pin "OUT") (pinfunction "2_OUT") (pintype "passive"))
      (node (ref "U$9") (pin "OUT") (pinfunction "2_OUT") (pintype "passive"))
    )
    (net (code "50") (name "/RF$3") (class "Default")
      (node (ref "B$10") (pin "OUT") (pinfunction "OUT_OUT") (pintype "bidirectional"))
      (node (ref "L$4") (pin "IN") (pinfunction "IN_IN") (pintype "passive"))
      (node (ref "U$8") (pin "IN") (pinfunction "1_IN") (pintype "passive"))
    )
    (net (code "51") (name "/RF$4") (class "Default")
      (node (ref "B$7") (pin "OUT") (pinfunction "OUT_OUT") (pintype "bidirectional"))
      (node (ref "L$1") (pin "IN") (pinfunction "IN_IN") (pintype "passive"))
      (node (ref "U$7") (pin "IN") (pinfunction "1_IN") (pintype "passive"))
    )
    (net (code "52") (name "Net-(B$1-PadHF)") (class "Default")
      (node (ref "B$1") (pin "HF") (pinfunction "HF_HF") (pintype "bidirectional"))
      (node (ref "S$7") (pin "1") (pinfunction "1_1") (pintype "passive"))
    )
    (net (code "53") (name "Net-(B$1-PadOUT)") (class "Default")
      (node (ref "B$1") (pin "OUT") (pinfunction "OUT_OUT") (pintype "bidirectional"))
      (node (ref "U$6") (pin "RF$02_G11") (pinfunction "RF$02_G11_RF$02_G11") (pintype "bidirectional"))
      (node (ref "U$6") (pin "RF$02_G12") (pinfunction "RF$02_G12_RF$02_G12") (pintype "bidirectional"))
    )
    (net (code "54") (name "Net-(B$2-PadHF)") (class "Default")
      (node (ref "B$2") (pin "HF") (pinfunction "HF_HF") (pintype "bidirectional"))
      (node (ref "S$6") (pin "1") (pinfunction "1_1") (pintype "passive"))
    )
    (net (code "55") (name "Net-(B$2-PadOUT)") (class "Default")
      (node (ref "B$2") (pin "OUT") (pinfunction "OUT_OUT") (pintype "bidirectional"))
      (node (ref "U$6") (pin "RF$04_G21") (pinfunction "RF$04_G21_RF$04_G21") (pintype "bidirectional"))
      (node (ref "U$6") (pin "RF$04_G22") (pinfunction "RF$04_G22_RF$04_G22") (pintype "bidirectional"))
    )
    (net (code "56") (name "Net-(B$3-PadHF)") (class "Default")
      (node (ref "B$3") (pin "HF") (pinfunction "HF_HF") (pintype "bidirectional"))
      (node (ref "S$4") (pin "1") (pinfunction "1_1") (pintype "passive"))
    )
    (net (code "57") (name "Net-(B$3-PadOUT)") (class "Default")
      (node (ref "B$3") (pin "OUT") (pinfunction "OUT_OUT") (pintype "bidirectional"))
      (node (ref "U$6") (pin "RF$09_G31") (pinfunction "RF$09_G31_RF$09_G31") (pintype "bidirectional"))
      (node (ref "U$6") (pin "RF$09_G32") (pinfunction "RF$09_G32_RF$09_G32") (pintype "bidirectional"))
      (node (ref "U$6") (pin "RF$09_G33") (pinfunction "RF$09_G33_RF$09_G33") (pintype "bidirectional"))
      (node (ref "U$6") (pin "RF$09_G34") (pinfunction "RF$09_G34_RF$09_G34") (pintype "bidirectional"))
    )
    (net (code "58") (name "Net-(B$4-PadHF)") (class "Default")
      (node (ref "B$4") (pin "HF") (pinfunction "HF_HF") (pintype "bidirectional"))
      (node (ref "S$3") (pin "1") (pinfunction "1_1") (pintype "passive"))
    )
    (net (code "59") (name "Net-(B$4-PadOUT)") (class "Default")
      (node (ref "B$4") (pin "OUT") (pinfunction "OUT_OUT") (pintype "bidirectional"))
      (node (ref "U$6") (pin "RF$14_G41") (pinfunction "RF$14_G41_RF$14_G41") (pintype "bidirectional"))
      (node (ref "U$6") (pin "RF$14_G42") (pinfunction "RF$14_G42_RF$14_G42") (pintype "bidirectional"))
    )
    (net (code "60") (name "Net-(B$5-PadHF)") (class "Default")
      (node (ref "B$5") (pin "HF") (pinfunction "HF_HF") (pintype "bidirectional"))
      (node (ref "S$2") (pin "1") (pinfunction "1_1") (pintype "passive"))
    )
    (net (code "61") (name "Net-(B$5-PadOUT)") (class "Default")
      (node (ref "B$5") (pin "OUT") (pinfunction "OUT_OUT") (pintype "bidirectional"))
      (node (ref "U$6") (pin "RF$16_G51") (pinfunction "RF$16_G51_RF$16_G51") (pintype "bidirectional"))
      (node (ref "U$6") (pin "RF$16_G52") (pinfunction "RF$16_G52_RF$16_G52") (pintype "bidirectional"))
    )
    (net (code "62") (name "Net-(B$6-PadHF)") (class "Default")
      (node (ref "B$6") (pin "HF") (pinfunction "HF_HF") (pintype "bidirectional"))
      (node (ref "S$1") (pin "1") (pinfunction "1_1") (pintype "passive"))
    )
    (net (code "63") (name "Net-(B$6-PadOUT)") (class "Default")
      (node (ref "B$6") (pin "OUT") (pinfunction "OUT_OUT") (pintype "bidirectional"))
      (node (ref "U$6") (pin "RF$21_G61") (pinfunction "RF$21_G61_RF$21_G61") (pintype "bidirectional"))
      (node (ref "U$6") (pin "RF$21_G62") (pinfunction "RF$21_G62_RF$21_G62") (pintype "bidirectional"))
      (node (ref "U$6") (pin "RF$21_G63") (pinfunction "RF$21_G63_RF$21_G63") (pintype "bidirectional"))
      (node (ref "U$6") (pin "RF$21_G64") (pinfunction "RF$21_G64_RF$21_G64") (pintype "bidirectional"))
    )
    (net (code "64") (name "Net-(R$1-2)") (class "Default")
      (node (ref "R$1") (pin "OUT") (pinfunction "2_OUT") (pintype "passive"))
      (node (ref "U$6") (pin "DC$01") (pinfunction "DC§01_DC$01") (pintype "bidirectional"))
    )
    (net (code "65") (name "Net-(R$3-2)") (class "Default")
      (node (ref "R$3") (pin "OUT") (pinfunction "2_OUT") (pintype "passive"))
      (node (ref "U$6") (pin "DC§03") (pinfunction "DC§03_DC§03") (pintype "bidirectional"))
    )
    (net (code "66") (name "Net-(R$6-2)") (class "Default")
      (node (ref "R$6") (pin "OUT") (pinfunction "2_OUT") (pintype "passive"))
      (node (ref "U$6") (pin "DC§06") (pinfunction "DC§06_DC§06") (pintype "bidirectional"))
    )
    (net (code "67") (name "Net-(R$7-2)") (class "Default")
      (node (ref "R$7") (pin "OUT") (pinfunction "2_OUT") (pintype "passive"))
      (node (ref "U$6") (pin "DC§08") (pinfunction "DC§08_DC§08") (pintype "bidirectional"))
    )
    (net (code "68") (name "Net-(R$9-2)") (class "Default")
      (node (ref "R$9") (pin "OUT") (pinfunction "2_OUT") (pintype "passive"))
      (node (ref "U$6") (pin "DC§10") (pinfunction "DC§10_DC§10") (pintype "bidirectional"))
    )
    (net (code "69") (name "Net-(R$10-2)") (class "Default")
      (node (ref "R$10") (pin "OUT") (pinfunction "2_OUT") (pintype "passive"))
      (node (ref "U$6") (pin "DC§11") (pinfunction "DC§11_DC§11") (pintype "bidirectional"))
    )
    (net (code "70") (name "Net-(R$11-2)") (class "Default")
      (node (ref "R$11") (pin "OUT") (pinfunction "2_OUT") (pintype "passive"))
      (node (ref "U$6") (pin "DC§12") (pinfunction "DC§12_DC§12") (pintype "bidirectional"))
    )
    (net (code "71") (name "Net-(R$12-2)") (class "Default")
      (node (ref "R$12") (pin "OUT") (pinfunction "2_OUT") (pintype "passive"))
      (node (ref "U$6") (pin "DC$13") (pinfunction "DC§13_DC$13") (pintype "bidirectional"))
    )
    (net (code "72") (name "Net-(R$19-2)") (class "Default")
      (node (ref "R$19") (pin "OUT") (pinfunction "2_OUT") (pintype "passive"))
      (node (ref "U$6") (pin "DC§19") (pinfunction "DC§019_DC§19") (pintype "bidirectional"))
    )
    (net (code "73") (name "Net-(R$20-2)") (class "Default")
      (node (ref "R$20") (pin "OUT") (pinfunction "2_OUT") (pintype "passive"))
      (node (ref "U$6") (pin "DC§20") (pinfunction "DC§20_DC§20") (pintype "bidirectional"))
    )
    (net (code "74") (name "Net-(R$22-2)") (class "Default")
      (node (ref "R$22") (pin "OUT") (pinfunction "2_OUT") (pintype "passive"))
      (node (ref "U$6") (pin "DC§22") (pinfunction "DC§22_DC§22") (pintype "bidirectional"))
    )
    (net (code "75") (name "Net-(R$23-2)") (class "Default")
      (node (ref "R$23") (pin "OUT") (pinfunction "2_OUT") (pintype "passive"))
      (node (ref "U$6") (pin "DC§23") (pinfunction "DC§23_DC§23") (pintype "bidirectional"))
    )
    (net (code "76") (name "Net-(R$24-2)") (class "Default")
      (node (ref "R$24") (pin "OUT") (pinfunction "2_OUT") (pintype "passive"))
      (node (ref "U$6") (pin "DC§24") (pinfunction "DC§24_DC§24") (pintype "bidirectional"))
    )
    (net (code "77") (name "Net-(R$25-2)") (class "Default")
      (node (ref "R$25") (pin "OUT") (pinfunction "2_OUT") (pintype "passive"))
      (node (ref "U$6") (pin "DC§07") (pinfunction "DC§07_DC§07") (pintype "bidirectional"))
    )
    (net (code "78") (name "Net-(R$29-2)") (class "Default")
      (node (ref "R$29") (pin "OUT") (pinfunction "2_OUT") (pintype "passive"))
      (node (ref "U$6") (pin "DC§17") (pinfunction "DC§17_DC§17") (pintype "bidirectional"))
    )
    (net (code "79") (name "Net-(R$30-2)") (class "Default")
      (node (ref "R$30") (pin "OUT") (pinfunction "2_OUT") (pintype "passive"))
      (node (ref "U$6") (pin "DC§18") (pinfunction "DC§18_DC§18") (pintype "bidirectional"))
    )
    (net (code "80") (name "Net-(U$3-IN)") (class "Default")
      (node (ref "U$3") (pin "P$1") (pinfunction "IN_P$1") (pintype "bidirectional"))
      (node (ref "U$4") (pin "P$3") (pinfunction "OUT2_P$3") (pintype "bidirectional"))
    )
    (net (code "81") (name "Net-(U$3-OUT1)") (class "Default")
      (node (ref "B$8") (pin "HF") (pinfunction "HF_HF") (pintype "bidirectional"))
      (node (ref "U$3") (pin "P$2") (pinfunction "OUT1_P$2") (pintype "bidirectional"))
    )
    (net (code "82") (name "Net-(U$3-OUT2)") (class "Default")
      (node (ref "B$7") (pin "HF") (pinfunction "HF_HF") (pintype "bidirectional"))
      (node (ref "U$3") (pin "P$3") (pinfunction "OUT2_P$3") (pintype "bidirectional"))
    )
    (net (code "83") (name "Net-(U$4-IN)") (class "Default")
      (node (ref "S$5") (pin "1") (pinfunction "1_1") (pintype "passive"))
      (node (ref "U$4") (pin "P$1") (pinfunction "IN_P$1") (pintype "bidirectional"))
    )
    (net (code "84") (name "Net-(U$4-OUT1)") (class "Default")
      (node (ref "U$4") (pin "P$2") (pinfunction "OUT1_P$2") (pintype "bidirectional"))
      (node (ref "U$5") (pin "P$1") (pinfunction "IN_P$1") (pintype "bidirectional"))
    )
    (net (code "85") (name "Net-(U$5-OUT1)") (class "Default")
      (node (ref "B$10") (pin "HF") (pinfunction "HF_HF") (pintype "bidirectional"))
      (node (ref "U$5") (pin "P$2") (pinfunction "OUT1_P$2") (pintype "bidirectional"))
    )
    (net (code "86") (name "Net-(U$5-OUT2)") (class "Default")
      (node (ref "B$9") (pin "HF") (pinfunction "HF_HF") (pintype "bidirectional"))
      (node (ref "U$5") (pin "P$3") (pinfunction "OUT2_P$3") (pintype "bidirectional"))
    )
    (net (code "87") (name "Net-(U$9-1)") (class "Default")
      (node (ref "B$9") (pin "OUT") (pinfunction "OUT_OUT") (pintype "bidirectional"))
      (node (ref "L$3") (pin "IN") (pinfunction "IN_IN") (pintype "passive"))
      (node (ref "U$9") (pin "IN") (pinfunction "1_IN") (pintype "passive"))
    )
    (net (code "88") (name "Net-(U$10-1)") (class "Default")
      (node (ref "B$8") (pin "OUT") (pinfunction "OUT_OUT") (pintype "bidirectional"))
      (node (ref "L$2") (pin "IN") (pinfunction "IN_IN") (pintype "passive"))
      (node (ref "U$10") (pin "IN") (pinfunction "1_IN") (pintype "passive"))
    )
    (net (code "89") (name "Net-(U$11-1)") (class "Default")
      (node (ref "L$4") (pin "OUT") (pinfunction "OUT_OUT") (pintype "passive"))
      (node (ref "U$11") (pin "IN") (pinfunction "1_IN") (pintype "passive"))
      (node (ref "U$6") (pin "RF$18_R3") (pinfunction "RF$18_R3_RF$18_R3") (pintype "bidirectional"))
    )
    (net (code "90") (name "Net-(U$12-1)") (class "Default")
      (node (ref "L$3") (pin "OUT") (pinfunction "OUT_OUT") (pintype "passive"))
      (node (ref "U$12") (pin "IN") (pinfunction "1_IN") (pintype "passive"))
      (node (ref "U$6") (pin "RF$12_R2") (pinfunction "RF$12_R2_RF$12_R2") (pintype "bidirectional"))
    )
    (net (code "91") (name "Net-(U$13-1)") (class "Default")
      (node (ref "L$2") (pin "OUT") (pinfunction "OUT_OUT") (pintype "passive"))
      (node (ref "U$13") (pin "IN") (pinfunction "1_IN") (pintype "passive"))
      (node (ref "U$6") (pin "RF$06_R1") (pinfunction "RF$06_R1_RF$06_R1") (pintype "bidirectional"))
    )
    (net (code "92") (name "Net-(U$14-1)") (class "Default")
      (node (ref "L$1") (pin "OUT") (pinfunction "OUT_OUT") (pintype "passive"))
      (node (ref "U$14") (pin "IN") (pinfunction "1_IN") (pintype "passive"))
      (node (ref "U$6") (pin "RF$24_R4") (pinfunction "RF$24_R4_RF$24_R4") (pintype "bidirectional"))
    )
    (net (code "93") (name "unconnected-(U$2-PadI$1)") (class "Default")
      (node (ref "U$2") (pin "I$1") (pinfunction "I$1_I$1") (pintype "bidirectional"))
    )
    (net (code "94") (name "unconnected-(U$2-PadI$2)") (class "Default")
      (node (ref "U$2") (pin "I$2") (pinfunction "I$2_I$2") (pintype "bidirectional"))
    )
    (net (code "95") (name "unconnected-(U$2-PadU$1)") (class "Default")
      (node (ref "U$2") (pin "U$1") (pinfunction "U$1_U$1") (pintype "bidirectional"))
    )
    (net (code "96") (name "unconnected-(U$2-PadU$2)") (class "Default")
      (node (ref "U$2") (pin "U$2") (pinfunction "U$2_U$2") (pintype "bidirectional"))
    )
  )
)
